# main_pcb.net
KiCad netlist of a schematic drawn in EAGLE
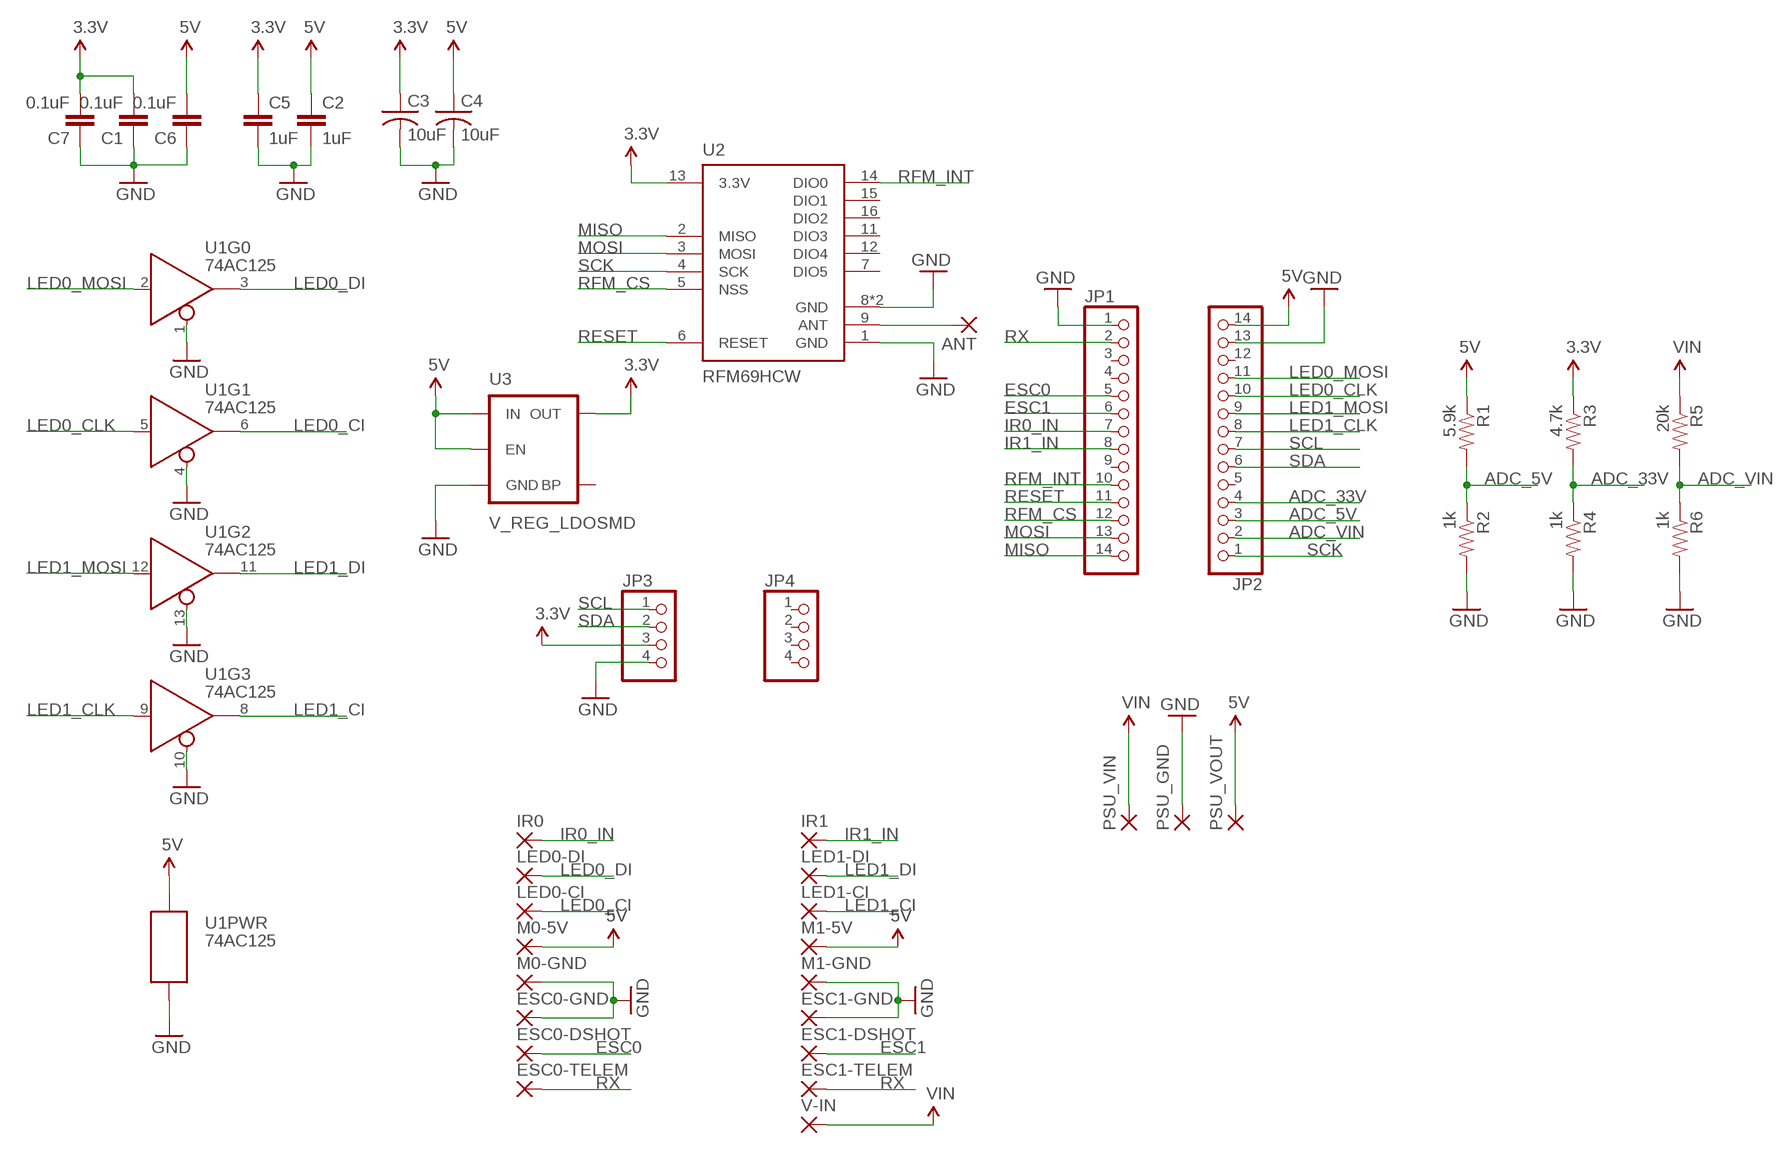
[diagram p0: schematic, sheet 1]

(export (version "E")
  (design (tool "Eeschema 10.0.6"))
  (components
    (comp (ref "ANT")
      (value "WIREPADSMD5-1,8")
      (footprint "eagle-import:5-1,8")
      (libsource (lib "eagle-import") (part "WIREPADSMD5-1,8"))
    )
    (comp (ref "C1")
      (value "0.1uF")
      (footprint "eagle-import:0805")
      (libsource (lib "eagle-import") (part "CAP0805"))
    )
    (comp (ref "C2")
      (value "1uF")
      (footprint "eagle-import:0805")
      (libsource (lib "eagle-import") (part "CAP0805"))
    )
    (comp (ref "C3")
      (value "10uF")
      (footprint "eagle-import:C1206")
      (libsource (lib "eagle-import") (part "C-USC1206"))
    )
    (comp (ref "C4")
      (value "10uF")
      (footprint "eagle-import:C1206")
      (libsource (lib "eagle-import") (part "C-USC1206"))
    )
    (comp (ref "C5")
      (value "1uF")
      (footprint "eagle-import:0805")
      (libsource (lib "eagle-import") (part "CAP0805"))
    )
    (comp (ref "C6")
      (value "0.1uF")
      (footprint "eagle-import:0805")
      (libsource (lib "eagle-import") (part "CAP0805"))
    )
    (comp (ref "C7")
      (value "0.1uF")
      (footprint "eagle-import:0805")
      (libsource (lib "eagle-import") (part "CAP0805"))
    )
    (comp (ref "ESC0-DSHOT")
      (value "WIREPADSMD5-1,8")
      (footprint "eagle-import:5-1,8")
      (libsource (lib "eagle-import") (part "WIREPADSMD5-1,8"))
    )
    (comp (ref "ESC0-GND")
      (value "WIREPADSMD5-1,8")
      (footprint "eagle-import:5-1,8")
      (libsource (lib "eagle-import") (part "WIREPADSMD5-1,8"))
    )
    (comp (ref "ESC0-TELEM")
      (value "WIREPADSMD5-1,8")
      (footprint "eagle-import:5-1,8")
      (libsource (lib "eagle-import") (part "WIREPADSMD5-1,8"))
    )
    (comp (ref "ESC1-DSHOT")
      (value "WIREPADSMD5-1,8")
      (footprint "eagle-import:5-1,8")
      (libsource (lib "eagle-import") (part "WIREPADSMD5-1,8"))
    )
    (comp (ref "ESC1-GND")
      (value "WIREPADSMD5-1,8")
      (footprint "eagle-import:5-1,8")
      (libsource (lib "eagle-import") (part "WIREPADSMD5-1,8"))
    )
    (comp (ref "ESC1-TELEM")
      (value "WIREPADSMD5-1,8")
      (footprint "eagle-import:5-1,8")
      (libsource (lib "eagle-import") (part "WIREPADSMD5-1,8"))
    )
    (comp (ref "IR0")
      (value "WIREPADSMD5-1,8")
      (footprint "eagle-import:5-1,8")
      (libsource (lib "eagle-import") (part "WIREPADSMD5-1,8"))
    )
    (comp (ref "IR1")
      (value "WIREPADSMD5-1,8")
      (footprint "eagle-import:5-1,8")
      (libsource (lib "eagle-import") (part "WIREPADSMD5-1,8"))
    )
    (comp (ref "JP1")
      (value "PINHD-1X141X14_SMT")
      (footprint "eagle-import:1X14_SMT")
      (libsource (lib "eagle-import") (part "PINHD-1X141X14_SMT"))
    )
    (comp (ref "JP2")
      (value "PINHD-1X141X14_SMT")
      (footprint "eagle-import:1X14_SMT")
      (libsource (lib "eagle-import") (part "PINHD-1X141X14_SMT"))
    )
    (comp (ref "JP3")
      (value "PINHD-1X41X04_SMT")
      (footprint "eagle-import:1X04_SMT")
      (libsource (lib "eagle-import") (part "PINHD-1X41X04_SMT"))
    )
    (comp (ref "JP4")
      (value "PINHD-1X41X04_SMT")
      (footprint "eagle-import:1X04_SMT")
      (libsource (lib "eagle-import") (part "PINHD-1X41X04_SMT"))
    )
    (comp (ref "LED0-CI")
      (value "WIREPADSMD5-1,8")
      (footprint "eagle-import:5-1,8")
      (libsource (lib "eagle-import") (part "WIREPADSMD5-1,8"))
    )
    (comp (ref "LED0-DI")
      (value "WIREPADSMD5-1,8")
      (footprint "eagle-import:5-1,8")
      (libsource (lib "eagle-import") (part "WIREPADSMD5-1,8"))
    )
    (comp (ref "LED1-CI")
      (value "WIREPADSMD5-1,8")
      (footprint "eagle-import:5-1,8")
      (libsource (lib "eagle-import") (part "WIREPADSMD5-1,8"))
    )
    (comp (ref "LED1-DI")
      (value "WIREPADSMD5-1,8")
      (footprint "eagle-import:5-1,8")
      (libsource (lib "eagle-import") (part "WIREPADSMD5-1,8"))
    )
    (comp (ref "M0-5V")
      (value "WIREPADSMD5-1,8")
      (footprint "eagle-import:5-1,8")
      (libsource (lib "eagle-import") (part "WIREPADSMD5-1,8"))
    )
    (comp (ref "M0-GND")
      (value "WIREPADSMD5-1,8")
      (footprint "eagle-import:5-1,8")
      (libsource (lib "eagle-import") (part "WIREPADSMD5-1,8"))
    )
    (comp (ref "M1-5V")
      (value "WIREPADSMD5-1,8")
      (footprint "eagle-import:5-1,8")
      (libsource (lib "eagle-import") (part "WIREPADSMD5-1,8"))
    )
    (comp (ref "M1-GND")
      (value "WIREPADSMD5-1,8")
      (footprint "eagle-import:5-1,8")
      (libsource (lib "eagle-import") (part "WIREPADSMD5-1,8"))
    )
    (comp (ref "PSU_GND")
      (value "WIREPADSMD5-1,8")
      (footprint "eagle-import:5-1,8")
      (libsource (lib "eagle-import") (part "WIREPADSMD5-1,8"))
    )
    (comp (ref "PSU_VIN")
      (value "WIREPADSMD5-1,8")
      (footprint "eagle-import:5-1,8")
      (libsource (lib "eagle-import") (part "WIREPADSMD5-1,8"))
    )
    (comp (ref "PSU_VOUT")
      (value "WIREPADSMD5-1,8")
      (footprint "eagle-import:5-1,8")
      (libsource (lib "eagle-import") (part "WIREPADSMD5-1,8"))
    )
    (comp (ref "R1")
      (value "5.9k")
      (footprint "eagle-import:0805")
      (libsource (lib "eagle-import") (part "RESISTOR0805-RES"))
    )
    (comp (ref "R2")
      (value "1k")
      (footprint "eagle-import:0805")
      (libsource (lib "eagle-import") (part "RESISTOR0805-RES"))
    )
    (comp (ref "R3")
      (value "4.7k")
      (footprint "eagle-import:0805")
      (libsource (lib "eagle-import") (part "RESISTOR0805-RES"))
    )
    (comp (ref "R4")
      (value "1k")
      (footprint "eagle-import:0805")
      (libsource (lib "eagle-import") (part "RESISTOR0805-RES"))
    )
    (comp (ref "R5")
      (value "20k")
      (footprint "eagle-import:0805")
      (libsource (lib "eagle-import") (part "RESISTOR0805-RES"))
    )
    (comp (ref "R6")
      (value "1k")
      (footprint "eagle-import:0805")
      (libsource (lib "eagle-import") (part "RESISTOR0805-RES"))
    )
    (comp (ref "U1")
      (value "74AC125")
      (footprint "eagle-import:SO14")
      (libsource (lib "eagle-import") (part "74125AC125DG"))
    )
    (comp (ref "U2")
      (value "RFM69HCW")
      (footprint "eagle-import:RFM69HCW-XXXS2")
      (libsource (lib "eagle-import") (part "RFM69HCW"))
    )
    (comp (ref "U3")
      (value "V_REG_LDOSMD")
      (footprint "eagle-import:SOT23-5")
      (libsource (lib "eagle-import") (part "V_REG_LDOSMD"))
    )
    (comp (ref "V-IN")
      (value "WIREPADSMD5-1,8")
      (footprint "eagle-import:5-1,8")
      (libsource (lib "eagle-import") (part "WIREPADSMD5-1,8"))
    )
  )
  (nets
    (net (code "1") (name "/ADC_5V") (class "Default")
      (node (ref "JP2") (pin "3") (pinfunction "3_3") (pintype "passive"))
      (node (ref "R1") (pin "2") (pinfunction "2_2") (pintype "passive"))
      (node (ref "R2") (pin "1") (pinfunction "1_1") (pintype "passive"))
    )
    (net (code "2") (name "/ADC_33V") (class "Default")
      (node (ref "JP2") (pin "4") (pinfunction "4_4") (pintype "passive"))
      (node (ref "R3") (pin "2") (pinfunction "2_2") (pintype "passive"))
      (node (ref "R4") (pin "1") (pinfunction "1_1") (pintype "passive"))
    )
    (net (code "3") (name "/ADC_VIN") (class "Default")
      (node (ref "JP2") (pin "2") (pinfunction "2_2") (pintype "passive"))
      (node (ref "R5") (pin "2") (pinfunction "2_2") (pintype "passive"))
      (node (ref "R6") (pin "1") (pinfunction "1_1") (pintype "passive"))
    )
    (net (code "4") (name "/ESC0") (class "Default")
      (node (ref "ESC0-DSHOT") (pin "1") (pinfunction "P_1") (pintype "passive"))
      (node (ref "JP1") (pin "5") (pinfunction "5_5") (pintype "passive"))
    )
    (net (code "5") (name "/ESC1") (class "Default")
      (node (ref "ESC1-DSHOT") (pin "1") (pinfunction "P_1") (pintype "passive"))
      (node (ref "JP1") (pin "6") (pinfunction "6_6") (pintype "passive"))
    )
    (net (code "6") (name "/IR0_IN") (class "Default")
      (node (ref "IR0") (pin "1") (pinfunction "P_1") (pintype "passive"))
      (node (ref "JP1") (pin "7") (pinfunction "7_7") (pintype "passive"))
    )
    (net (code "7") (name "/IR1_IN") (class "Default")
      (node (ref "IR1") (pin "1") (pinfunction "P_1") (pintype "passive"))
      (node (ref "JP1") (pin "8") (pinfunction "8_8") (pintype "passive"))
    )
    (net (code "8") (name "/LED0_CI") (class "Default")
      (node (ref "LED0-CI") (pin "1") (pinfunction "P_1") (pintype "passive"))
      (node (ref "U1") (pin "6") (pinfunction "Q_6") (pintype "bidirectional"))
    )
    (net (code "9") (name "/LED0_CLK") (class "Default")
      (node (ref "JP2") (pin "10") (pinfunction "10_10") (pintype "passive"))
      (node (ref "U1") (pin "5") (pinfunction "D_5") (pintype "bidirectional"))
    )
    (net (code "10") (name "/LED0_DI") (class "Default")
      (node (ref "LED0-DI") (pin "1") (pinfunction "P_1") (pintype "passive"))
      (node (ref "U1") (pin "3") (pinfunction "Q_3") (pintype "bidirectional"))
    )
    (net (code "11") (name "/LED0_MOSI") (class "Default")
      (node (ref "JP2") (pin "11") (pinfunction "11_11") (pintype "passive"))
      (node (ref "U1") (pin "2") (pinfunction "D_2") (pintype "bidirectional"))
    )
    (net (code "12") (name "/LED1_CI") (class "Default")
      (node (ref "LED1-CI") (pin "1") (pinfunction "P_1") (pintype "passive"))
      (node (ref "U1") (pin "8") (pinfunction "Q_8") (pintype "bidirectional"))
    )
    (net (code "13") (name "/LED1_CLK") (class "Default")
      (node (ref "JP2") (pin "8") (pinfunction "8_8") (pintype "passive"))
      (node (ref "U1") (pin "9") (pinfunction "D_9") (pintype "bidirectional"))
    )
    (net (code "14") (name "/LED1_DI") (class "Default")
      (node (ref "LED1-DI") (pin "1") (pinfunction "P_1") (pintype "passive"))
      (node (ref "U1") (pin "11") (pinfunction "Q_11") (pintype "bidirectional"))
    )
    (net (code "15") (name "/LED1_MOSI") (class "Default")
      (node (ref "JP2") (pin "9") (pinfunction "9_9") (pintype "passive"))
      (node (ref "U1") (pin "12") (pinfunction "D_12") (pintype "bidirectional"))
    )
    (net (code "16") (name "/MISO") (class "Default")
      (node (ref "JP1") (pin "14") (pinfunction "14_14") (pintype "passive"))
      (node (ref "U2") (pin "2") (pinfunction "MISO_2") (pintype "bidirectional"))
    )
    (net (code "17") (name "/MOSI") (class "Default")
      (node (ref "JP1") (pin "13") (pinfunction "13_13") (pintype "passive"))
      (node (ref "U2") (pin "3") (pinfunction "MOSI_3") (pintype "input"))
    )
    (net (code "18") (name "/RESET") (class "Default")
      (node (ref "JP1") (pin "11") (pinfunction "11_11") (pintype "passive"))
      (node (ref "U2") (pin "6") (pinfunction "RESET_6") (pintype "input"))
    )
    (net (code "19") (name "/RFM_CS") (class "Default")
      (node (ref "JP1") (pin "12") (pinfunction "12_12") (pintype "passive"))
      (node (ref "U2") (pin "5") (pinfunction "NSS_5") (pintype "input"))
    )
    (net (code "20") (name "/RFM_INT") (class "Default")
      (node (ref "JP1") (pin "10") (pinfunction "10_10") (pintype "passive"))
      (node (ref "U2") (pin "14") (pinfunction "DIO0_14") (pintype "bidirectional"))
    )
    (net (code "21") (name "/RX") (class "Default")
      (node (ref "ESC0-TELEM") (pin "1") (pinfunction "P_1") (pintype "passive"))
      (node (ref "ESC1-TELEM") (pin "1") (pinfunction "P_1") (pintype "passive"))
      (node (ref "JP1") (pin "2") (pinfunction "2_2") (pintype "passive"))
    )
    (net (code "22") (name "/SCK") (class "Default")
      (node (ref "JP2") (pin "1") (pinfunction "1_1") (pintype "passive"))
      (node (ref "U2") (pin "4") (pinfunction "SCK_4") (pintype "input"))
    )
    (net (code "23") (name "/SCL") (class "Default")
      (node (ref "JP2") (pin "7") (pinfunction "7_7") (pintype "passive"))
      (node (ref "JP3") (pin "1") (pinfunction "1_1") (pintype "passive"))
    )
    (net (code "24") (name "/SDA") (class "Default")
      (node (ref "JP2") (pin "6") (pinfunction "6_6") (pintype "passive"))
      (node (ref "JP3") (pin "2") (pinfunction "2_2") (pintype "passive"))
    )
    (net (code "25") (name "3.3V") (class "Default")
      (node (ref "C1") (pin "2") (pinfunction "2_2") (pintype "passive"))
      (node (ref "C3") (pin "1") (pinfunction "1_1") (pintype "passive"))
      (node (ref "C5") (pin "1") (pinfunction "1_1") (pintype "passive"))
      (node (ref "C7") (pin "2") (pinfunction "2_2") (pintype "passive"))
      (node (ref "JP3") (pin "3") (pinfunction "3_3") (pintype "passive"))
      (node (ref "R3") (pin "1") (pinfunction "1_1") (pintype "passive"))
      (node (ref "U2") (pin "13") (pinfunction "3.3V_13") (pintype "power_in"))
      (node (ref "U3") (pin "5") (pinfunction "OUT_5") (pintype "passive"))
    )
    (net (code "26") (name "5V") (class "Default")
      (node (ref "C2") (pin "1") (pinfunction "1_1") (pintype "passive"))
      (node (ref "C4") (pin "1") (pinfunction "1_1") (pintype "passive"))
      (node (ref "C6") (pin "2") (pinfunction "2_2") (pintype "passive"))
      (node (ref "JP2") (pin "14") (pinfunction "14_14") (pintype "passive"))
      (node (ref "M0-5V") (pin "1") (pinfunction "P_1") (pintype "passive"))
      (node (ref "M1-5V") (pin "1") (pinfunction "P_1") (pintype "passive"))
      (node (ref "PSU_VOUT") (pin "1") (pinfunction "P_1") (pintype "passive"))
      (node (ref "R1") (pin "1") (pinfunction "1_1") (pintype "passive"))
      (node (ref "U1") (pin "14") (pinfunction "P$V+_14") (pintype "bidirectional"))
      (node (ref "U3") (pin "1") (pinfunction "IN_1") (pintype "input"))
      (node (ref "U3") (pin "3") (pinfunction "EN_3") (pintype "input"))
    )
    (net (code "27") (name "GND") (class "Default")
      (node (ref "C1") (pin "1") (pinfunction "1_1") (pintype "passive"))
      (node (ref "C2") (pin "2") (pinfunction "2_2") (pintype "passive"))
      (node (ref "C3") (pin "2") (pinfunction "2_2") (pintype "passive"))
      (node (ref "C4") (pin "2") (pinfunction "2_2") (pintype "passive"))
      (node (ref "C5") (pin "2") (pinfunction "2_2") (pintype "passive"))
      (node (ref "C6") (pin "1") (pinfunction "1_1") (pintype "passive"))
      (node (ref "C7") (pin "1") (pinfunction "1_1") (pintype "passive"))
      (node (ref "ESC0-GND") (pin "1") (pinfunction "P_1") (pintype "passive"))
      (node (ref "ESC1-GND") (pin "1") (pinfunction "P_1") (pintype "passive"))
      (node (ref "JP1") (pin "1") (pinfunction "1_1") (pintype "passive"))
      (node (ref "JP2") (pin "13") (pinfunction "13_13") (pintype "passive"))
      (node (ref "JP3") (pin "4") (pinfunction "4_4") (pintype "passive"))
      (node (ref "M0-GND") (pin "1") (pinfunction "P_1") (pintype "passive"))
      (node (ref "M1-GND") (pin "1") (pinfunction "P_1") (pintype "passive"))
      (node (ref "PSU_GND") (pin "1") (pinfunction "P_1") (pintype "passive"))
      (node (ref "R2") (pin "2") (pinfunction "2_2") (pintype "passive"))
      (node (ref "R4") (pin "2") (pinfunction "2_2") (pintype "passive"))
      (node (ref "R6") (pin "2") (pinfunction "2_2") (pintype "passive"))
      (node (ref "U1") (pin "1") (pinfunction "~{EN}_1") (pintype "bidirectional"))
      (node (ref "U1") (pin "10") (pinfunction "~{EN}_10") (pintype "bidirectional"))
      (node (ref "U1") (pin "13") (pinfunction "~{EN}_13") (pintype "bidirectional"))
      (node (ref "U1") (pin "4") (pinfunction "~{EN}_4") (pintype "bidirectional"))
      (node (ref "U1") (pin "7") (pinfunction "P$V-_7") (pintype "bidirectional"))
      (node (ref "U2") (pin "1") (pinfunction "GND_1") (pintype "power_in"))
      (node (ref "U2") (pin "10") (pinfunction "GND_10") (pintype "power_in"))
      (node (ref "U2") (pin "8") (pinfunction "GND_8") (pintype "power_in"))
      (node (ref "U3") (pin "2") (pinfunction "GND_2") (pintype "input"))
    )
    (net (code "28") (name "Net-(ANT-P)") (class "Default")
      (node (ref "ANT") (pin "1") (pinfunction "P_1") (pintype "passive"))
      (node (ref "U2") (pin "9") (pinfunction "ANT_9") (pintype "passive"))
    )
    (net (code "29") (name "VIN") (class "Default")
      (node (ref "PSU_VIN") (pin "1") (pinfunction "P_1") (pintype "passive"))
      (node (ref "R5") (pin "1") (pinfunction "1_1") (pintype "passive"))
      (node (ref "V-IN") (pin "1") (pinfunction "P_1") (pintype "passive"))
    )
    (net (code "30") (name "unconnected-(JP1-Pad3)") (class "Default")
      (node (ref "JP1") (pin "3") (pinfunction "3_3") (pintype "passive"))
    )
    (net (code "31") (name "unconnected-(JP1-Pad4)") (class "Default")
      (node (ref "JP1") (pin "4") (pinfunction "4_4") (pintype "passive"))
    )
    (net (code "32") (name "unconnected-(JP1-Pad9)") (class "Default")
      (node (ref "JP1") (pin "9") (pinfunction "9_9") (pintype "passive"))
    )
    (net (code "33") (name "unconnected-(JP2-Pad5)") (class "Default")
      (node (ref "JP2") (pin "5") (pinfunction "5_5") (pintype "passive"))
    )
    (net (code "34") (name "unconnected-(JP2-Pad12)") (class "Default")
      (node (ref "JP2") (pin "12") (pinfunction "12_12") (pintype "passive"))
    )
    (net (code "35") (name "unconnected-(JP4-Pad1)") (class "Default")
      (node (ref "JP4") (pin "1") (pinfunction "1_1") (pintype "passive"))
    )
    (net (code "36") (name "unconnected-(JP4-Pad2)") (class "Default")
      (node (ref "JP4") (pin "2") (pinfunction "2_2") (pintype "passive"))
    )
    (net (code "37") (name "unconnected-(JP4-Pad3)") (class "Default")
      (node (ref "JP4") (pin "3") (pinfunction "3_3") (pintype "passive"))
    )
    (net (code "38") (name "unconnected-(JP4-Pad4)") (class "Default")
      (node (ref "JP4") (pin "4") (pinfunction "4_4") (pintype "passive"))
    )
    (net (code "39") (name "unconnected-(U2-DIO1-Pad15)") (class "Default")
      (node (ref "U2") (pin "15") (pinfunction "DIO1_15") (pintype "bidirectional"))
    )
    (net (code "40") (name "unconnected-(U2-DIO2-Pad16)") (class "Default")
      (node (ref "U2") (pin "16") (pinfunction "DIO2_16") (pintype "bidirectional"))
    )
    (net (code "41") (name "unconnected-(U2-DIO3-Pad11)") (class "Default")
      (node (ref "U2") (pin "11") (pinfunction "DIO3_11") (pintype "bidirectional"))
    )
    (net (code "42") (name "unconnected-(U2-DIO4-Pad12)") (class "Default")
      (node (ref "U2") (pin "12") (pinfunction "DIO4_12") (pintype "bidirectional"))
    )
    (net (code "43") (name "unconnected-(U2-DIO5-Pad7)") (class "Default")
      (node (ref "U2") (pin "7") (pinfunction "DIO5_7") (pintype "bidirectional"))
    )
    (net (code "44") (name "unconnected-(U3-BP-Pad4)") (class "Default")
      (node (ref "U3") (pin "4") (pinfunction "BP_4") (pintype "input"))
    )
  )
)
